# Arduino-TPUART.net
KiCad netlist of a schematic drawn in EAGLE
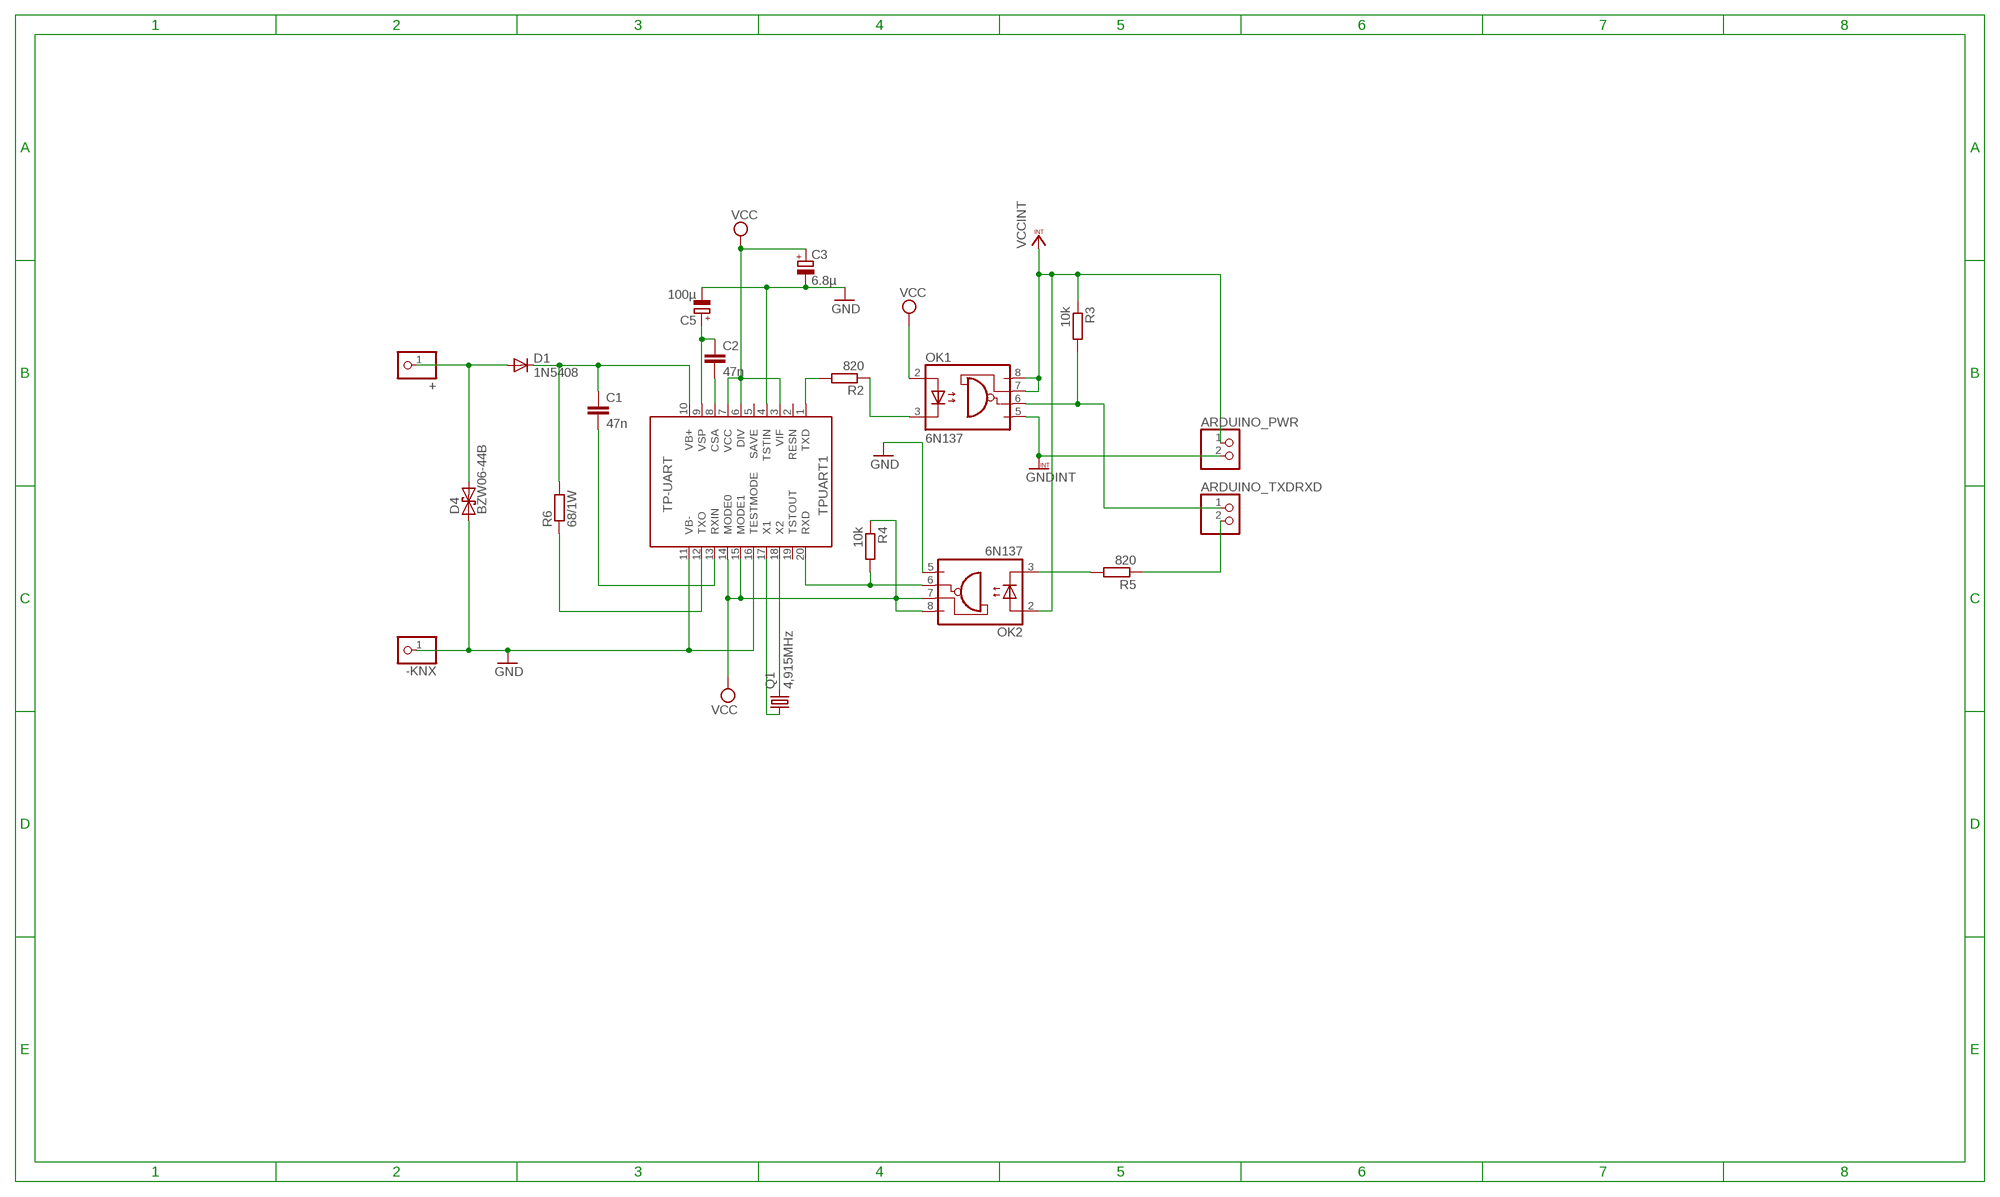
[diagram p0: schematic, sheet 1]

(export (version "E")
  (design (tool "Eeschema 10.0.6"))
  (components
    (comp (ref "+")
      (value "PINHD-1X1")
      (footprint "eagle-import:1X01")
      (libsource (lib "eagle-import") (part "PINHD-1X1"))
    )
    (comp (ref "-KNX")
      (value "PINHD-1X1")
      (footprint "eagle-import:1X01")
      (libsource (lib "eagle-import") (part "PINHD-1X1"))
    )
    (comp (ref "ARDUINO_PWR")
      (value "PINHD-1X2")
      (footprint "eagle-import:1X02")
      (libsource (lib "eagle-import") (part "PINHD-1X2"))
    )
    (comp (ref "ARDUINO_TXDRXD")
      (value "PINHD-1X2")
      (footprint "eagle-import:1X02")
      (libsource (lib "eagle-import") (part "PINHD-1X2"))
    )
    (comp (ref "C1")
      (value "47n")
      (footprint "eagle-import:C025-025X050")
      (libsource (lib "eagle-import") (part "C-EU025-025X050"))
    )
    (comp (ref "C2")
      (value "47n")
      (footprint "eagle-import:C025-025X050")
      (libsource (lib "eagle-import") (part "C-EU025-025X050"))
    )
    (comp (ref "C3")
      (value "6.8µ")
      (footprint "eagle-import:E2-5")
      (libsource (lib "eagle-import") (part "CPOL-EUE2-5"))
    )
    (comp (ref "C5")
      (value "100µ")
      (footprint "eagle-import:E2,5-5")
      (libsource (lib "eagle-import") (part "CPOL-EUE2.5-5"))
    )
    (comp (ref "D1")
      (value "1N5408")
      (footprint "eagle-import:DO201-15")
      (libsource (lib "eagle-import") (part "1N5400"))
    )
    (comp (ref "D4")
      (value "BZW06-44B")
      (footprint "eagle-import:F126Z12")
      (libsource (lib "eagle-import") (part "BZW04XXB"))
    )
    (comp (ref "OK1")
      (value "6N137")
      (footprint "eagle-import:DIL08")
      (libsource (lib "eagle-import") (part "6N137"))
    )
    (comp (ref "OK2")
      (value "6N137")
      (footprint "eagle-import:DIL08")
      (libsource (lib "eagle-import") (part "6N137"))
    )
    (comp (ref "Q1")
      (value "4,915MHz")
      (footprint "eagle-import:HC18U-V")
      (libsource (lib "eagle-import") (part "CRYSTALHC18U-V"))
    )
    (comp (ref "R2")
      (value "820")
      (footprint "eagle-import:0411_12")
      (libsource (lib "eagle-import") (part "R-EU_0411/12"))
    )
    (comp (ref "R3")
      (value "10k")
      (footprint "eagle-import:0411_12")
      (libsource (lib "eagle-import") (part "R-EU_0411/12"))
    )
    (comp (ref "R4")
      (value "10k")
      (footprint "eagle-import:0411_12")
      (libsource (lib "eagle-import") (part "R-EU_0411/12"))
    )
    (comp (ref "R5")
      (value "820")
      (footprint "eagle-import:0411_12")
      (libsource (lib "eagle-import") (part "R-EU_0411/12"))
    )
    (comp (ref "R6")
      (value "68/1W")
      (footprint "eagle-import:0414_15")
      (libsource (lib "eagle-import") (part "R-EU_0414/15"))
    )
    (comp (ref "TPUART1")
      (value "TP-UART")
      (footprint "eagle-import:SOIC20")
      (libsource (lib "eagle-import") (part "TP-UART"))
    )
  )
  (nets
    (net (code "1") (name "GND") (class "Default")
      (node (ref "-KNX") (pin "1") (pinfunction "1_1") (pintype "passive"))
      (node (ref "C3") (pin "-") (pinfunction "-_-") (pintype "passive"))
      (node (ref "C5") (pin "-") (pinfunction "-_-") (pintype "passive"))
      (node (ref "D4") (pin "A") (pinfunction "1_A") (pintype "passive"))
      (node (ref "OK2") (pin "5") (pinfunction "GND_5") (pintype "passive"))
      (node (ref "TPUART1") (pin "11") (pinfunction "VB-_11") (pintype "passive"))
      (node (ref "TPUART1") (pin "16") (pinfunction "TESTMODE_16") (pintype "input"))
      (node (ref "TPUART1") (pin "4") (pinfunction "TSTIN_4") (pintype "bidirectional"))
    )
    (net (code "2") (name "GNDINT") (class "Default")
      (node (ref "ARDUINO_PWR") (pin "2") (pinfunction "2_2") (pintype "passive"))
      (node (ref "OK1") (pin "5") (pinfunction "GND_5") (pintype "passive"))
    )
    (net (code "3") (name "Net-(ARDUINO_TXDRXD-Pad2)") (class "Default")
      (node (ref "ARDUINO_TXDRXD") (pin "2") (pinfunction "2_2") (pintype "passive"))
      (node (ref "R5") (pin "1") (pinfunction "1_1") (pintype "passive"))
    )
    (net (code "4") (name "Net-(D4-2)") (class "Default")
      (node (ref "+") (pin "1") (pinfunction "1_1") (pintype "passive"))
      (node (ref "D1") (pin "A") (pinfunction "A_A") (pintype "passive"))
      (node (ref "D4") (pin "C") (pinfunction "2_C") (pintype "passive"))
    )
    (net (code "5") (name "Net-(OK1-C)") (class "Default")
      (node (ref "OK1") (pin "3") (pinfunction "C_3") (pintype "passive"))
      (node (ref "R2") (pin "1") (pinfunction "1_1") (pintype "passive"))
    )
    (net (code "6") (name "Net-(OK1-VO)") (class "Default")
      (node (ref "ARDUINO_TXDRXD") (pin "1") (pinfunction "1_1") (pintype "passive"))
      (node (ref "OK1") (pin "6") (pinfunction "VO_6") (pintype "passive"))
      (node (ref "R3") (pin "2") (pinfunction "2_2") (pintype "passive"))
    )
    (net (code "7") (name "Net-(OK2-C)") (class "Default")
      (node (ref "OK2") (pin "3") (pinfunction "C_3") (pintype "passive"))
      (node (ref "R5") (pin "2") (pinfunction "2_2") (pintype "passive"))
    )
    (net (code "8") (name "Net-(OK2-VO)") (class "Default")
      (node (ref "OK2") (pin "6") (pinfunction "VO_6") (pintype "passive"))
      (node (ref "R4") (pin "2") (pinfunction "2_2") (pintype "passive"))
      (node (ref "TPUART1") (pin "20") (pinfunction "RXD_20") (pintype "input"))
    )
    (net (code "9") (name "Net-(TPUART1-CSA)") (class "Default")
      (node (ref "C2") (pin "2") (pinfunction "2_2") (pintype "passive"))
      (node (ref "TPUART1") (pin "8") (pinfunction "CSA_8") (pintype "passive"))
    )
    (net (code "10") (name "Net-(TPUART1-RXIN)") (class "Default")
      (node (ref "C1") (pin "2") (pinfunction "2_2") (pintype "passive"))
      (node (ref "TPUART1") (pin "13") (pinfunction "RXIN_13") (pintype "input"))
    )
    (net (code "11") (name "Net-(TPUART1-TXD)") (class "Default")
      (node (ref "R2") (pin "2") (pinfunction "2_2") (pintype "passive"))
      (node (ref "TPUART1") (pin "1") (pinfunction "TXD_1") (pintype "output"))
    )
    (net (code "12") (name "Net-(TPUART1-TXO)") (class "Default")
      (node (ref "R6") (pin "1") (pinfunction "1_1") (pintype "passive"))
      (node (ref "TPUART1") (pin "12") (pinfunction "TXO_12") (pintype "output"))
    )
    (net (code "13") (name "Net-(TPUART1-VB+)") (class "Default")
      (node (ref "C1") (pin "1") (pinfunction "1_1") (pintype "passive"))
      (node (ref "D1") (pin "C") (pinfunction "C_C") (pintype "passive"))
      (node (ref "R6") (pin "2") (pinfunction "2_2") (pintype "passive"))
      (node (ref "TPUART1") (pin "10") (pinfunction "VB+_10") (pintype "passive"))
    )
    (net (code "14") (name "Net-(TPUART1-VSP)") (class "Default")
      (node (ref "C2") (pin "1") (pinfunction "1_1") (pintype "passive"))
      (node (ref "C5") (pin "+") (pinfunction "+_+") (pintype "passive"))
      (node (ref "TPUART1") (pin "9") (pinfunction "VSP_9") (pintype "passive"))
    )
    (net (code "15") (name "Net-(TPUART1-X1)") (class "Default")
      (node (ref "Q1") (pin "1") (pinfunction "1_1") (pintype "passive"))
      (node (ref "TPUART1") (pin "17") (pinfunction "X1_17") (pintype "passive"))
    )
    (net (code "16") (name "Net-(TPUART1-X2)") (class "Default")
      (node (ref "Q1") (pin "2") (pinfunction "2_2") (pintype "passive"))
      (node (ref "TPUART1") (pin "18") (pinfunction "X2_18") (pintype "passive"))
    )
    (net (code "17") (name "VCC") (class "Default")
      (node (ref "C3") (pin "+") (pinfunction "+_+") (pintype "passive"))
      (node (ref "OK1") (pin "2") (pinfunction "A_2") (pintype "passive"))
      (node (ref "OK2") (pin "7") (pinfunction "VE_7") (pintype "passive"))
      (node (ref "OK2") (pin "8") (pinfunction "VCC_8") (pintype "passive"))
      (node (ref "R4") (pin "1") (pinfunction "1_1") (pintype "passive"))
      (node (ref "TPUART1") (pin "14") (pinfunction "MODE0_14") (pintype "input"))
      (node (ref "TPUART1") (pin "15") (pinfunction "MODE1_15") (pintype "input"))
      (node (ref "TPUART1") (pin "3") (pinfunction "VIF_3") (pintype "input"))
      (node (ref "TPUART1") (pin "6") (pinfunction "DIV_6") (pintype "input"))
      (node (ref "TPUART1") (pin "7") (pinfunction "VCC_7") (pintype "output"))
    )
    (net (code "18") (name "VCCINT") (class "Default")
      (node (ref "ARDUINO_PWR") (pin "1") (pinfunction "1_1") (pintype "passive"))
      (node (ref "OK1") (pin "7") (pinfunction "VE_7") (pintype "passive"))
      (node (ref "OK1") (pin "8") (pinfunction "VCC_8") (pintype "passive"))
      (node (ref "OK2") (pin "2") (pinfunction "A_2") (pintype "passive"))
      (node (ref "R3") (pin "1") (pinfunction "1_1") (pintype "passive"))
    )
    (net (code "19") (name "unconnected-(TPUART1-RESN-Pad2)") (class "Default")
      (node (ref "TPUART1") (pin "2") (pinfunction "RESN_2") (pintype "bidirectional"))
    )
    (net (code "20") (name "unconnected-(TPUART1-SAVE-Pad5)") (class "Default")
      (node (ref "TPUART1") (pin "5") (pinfunction "SAVE_5") (pintype "open_collector"))
    )
    (net (code "21") (name "unconnected-(TPUART1-TSTOUT-Pad19)") (class "Default")
      (node (ref "TPUART1") (pin "19") (pinfunction "TSTOUT_19") (pintype "output"))
    )
  )
)
